# Top.net
KiCad netlist of a schematic drawn in Altium Designer
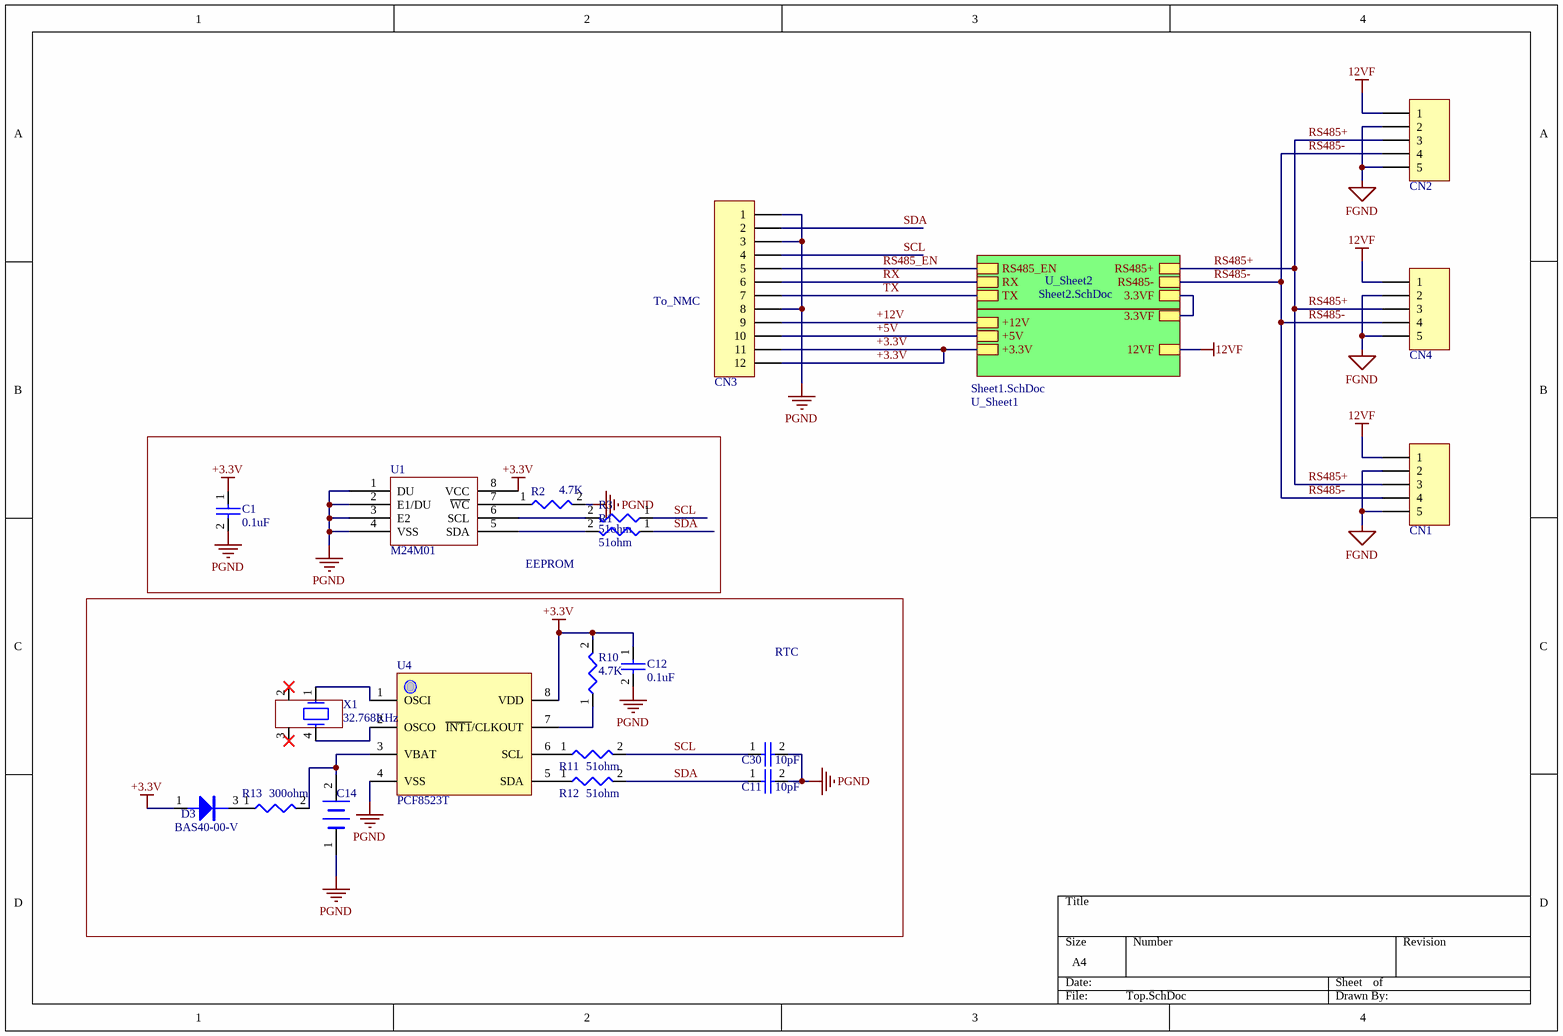
[diagram p0: Top.SchDoc]

(export (version "E")
  (design (tool "Eeschema 10.0.6"))
  (components
    (comp (ref "C1")
      (value "0.1uF")
      (footprint "C0805")
      (description "CAP SMD CR X7R 50V 10% 0.1uF 0805 ROHS")
      (fields (field (name "MANUFACTURER") "YAGEO") (field (name "Comment") "CAP"))
      (libsource (lib "enlogic") (part "CAP"))
    )
    (comp (ref "C11")
      (value "10pF")
      (footprint "C0805")
      (description "CAP SMD C0G 50V 10% 10pF 0805 ROHS")
      (fields (field (name "MANUFACTURER") "YAGEO") (field (name "Comment") "CAP"))
      (libsource (lib "enlogic") (part "CAP"))
    )
    (comp (ref "C12")
      (value "0.1uF")
      (footprint "C0805")
      (description "CAP SMD CR X7R 50V 10% 0.1uF 0805 ROHS")
      (fields (field (name "MANUFACTURER") "YAGEO") (field (name "Comment") "CAP"))
      (libsource (lib "enlogic") (part "CAP"))
    )
    (comp (ref "C14")
      (value "BATTERY")
      (footprint "DXJ_5R5H334U")
      (description "CAP Super Capacitor,5.5V 0.33F 11.5X5MM ROHS")
      (fields (field (name "MANUFACTURER") "ELNA"))
      (libsource (lib "enlogic") (part "BATTERY"))
    )
    (comp (ref "C30")
      (value "10pF")
      (footprint "C0805")
      (description "CAP SMD C0G 50V 10% 10pF 0805 ROHS")
      (fields (field (name "MANUFACTURER") "YAGEO") (field (name "Comment") "CAP"))
      (libsource (lib "enlogic") (part "CAP"))
    )
    (comp (ref "CN1")
      (value "Header 5")
      (footprint "70551-5P")
      (description "CONNECTOR 5PIN,2.54PITCH,90 Degrees,PTH")
      (fields (field (name "MANUFACTURER") "MOLEX"))
      (libsource (lib "enlogic") (part "Header 5"))
    )
    (comp (ref "CN2")
      (value "Header 5")
      (footprint "532590529")
      (description "CONNECTOR 5PIN,3.5PITCH,PTH,ROHS")
      (fields (field (name "MANUFACTURER") "MOLEX"))
      (libsource (lib "enlogic") (part "Header 5"))
    )
    (comp (ref "CN3")
      (value "Header 12")
      (footprint "353621276P2")
      (description "CONNECTOR 12PIN,2.00PITCH,PTH,2A,125V,ROHS,MATE_WITH:35507")
      (fields (field (name "MANUFACTURER") "MOLEX"))
      (libsource (lib "enlogic") (part "Header 12"))
    )
    (comp (ref "CN4")
      (value "Header 5")
      (footprint "70551-5P")
      (description "CONNECTOR 5PIN,2.54PITCH,90 Degrees,PTH")
      (fields (field (name "MANUFACTURER") "MOLEX"))
      (libsource (lib "enlogic") (part "Header 5"))
    )
    (comp (ref "D3")
      (value "BAS40-00-V")
      (footprint "SOT23-123")
      (description "DIODE Schottky Diode 40V 0.2A SOT-23 SMD ROHS")
      (fields (field (name "MANUFACTURER") "VISHAY"))
      (libsource (lib "enlogic") (part "BAS40-00-V"))
    )
    (comp (ref "R1")
      (value "51ohm")
      (footprint "R0805")
      (description "RES THICK_FILM SMD 51 OHM 5% 1/8W ROHS 0805")
      (fields (field (name "MANUFACTURER") "YAGEO") (field (name "Comment") "RES"))
      (libsource (lib "enlogic") (part "RES"))
    )
    (comp (ref "R2")
      (value "4.7K")
      (footprint "R0805")
      (description "RES THICK_FILM SMD 4.7K 5% 1/8W ROHS 0805")
      (fields (field (name "MANUFACTURER") "YAGEO") (field (name "Comment") "RES"))
      (libsource (lib "enlogic") (part "RES"))
    )
    (comp (ref "R3")
      (value "51ohm")
      (footprint "R0805")
      (description "RES THICK_FILM SMD 51 OHM 5% 1/8W ROHS 0805")
      (fields (field (name "MANUFACTURER") "YAGEO") (field (name "Comment") "RES"))
      (libsource (lib "enlogic") (part "RES"))
    )
    (comp (ref "R10")
      (value "4.7K")
      (footprint "R0805")
      (description "RES THICK_FILM SMD 4.7K 5% 1/8W ROHS 0805")
      (fields (field (name "MANUFACTURER") "YAGEO") (field (name "Comment") "RES"))
      (libsource (lib "enlogic") (part "RES"))
    )
    (comp (ref "R11")
      (value "51ohm")
      (footprint "R0805")
      (description "RES THICK_FILM SMD 51 OHM 5% 1/8W ROHS 0805")
      (fields (field (name "MANUFACTURER") "YAGEO") (field (name "Comment") "RES"))
      (libsource (lib "enlogic") (part "RES"))
    )
    (comp (ref "R12")
      (value "51ohm")
      (footprint "R0805")
      (description "RES THICK_FILM SMD 51 OHM 5% 1/8W ROHS 0805")
      (fields (field (name "MANUFACTURER") "YAGEO") (field (name "Comment") "RES"))
      (libsource (lib "enlogic") (part "RES"))
    )
    (comp (ref "R13")
      (value "300ohm")
      (footprint "R1206")
      (description "RES THICK_FILM SMD 300 OHM 1% 1/4W ROHS 1206")
      (fields (field (name "MANUFACTURER") "YAGEO") (field (name "Comment") "RES"))
      (libsource (lib "enlogic") (part "RES"))
    )
    (comp (ref "U1")
      (value "M24M01")
      (footprint "SOIC8")
      (description "IC 1-Mbit serial I2C bus EEPROM")
      (fields (field (name "MANUFACTURER") "ST"))
      (libsource (lib "enlogic") (part "M24M01"))
    )
    (comp (ref "U4")
      (value "PCF8523T")
      (footprint "SO-8")
      (description "IC Real-Time Clock (RTC) and calendar,SO8，ROHS")
      (fields (field (name "MANUFACTURER") "NXP"))
      (libsource (lib "enlogic") (part "PCF8523T"))
    )
    (comp (ref "X1")
      (value "32.768KHz")
      (footprint "MC306")
      (description "XTAL 8.0*3.8*2.5 32.768KHZ 6PF, +/-20PPM,SMD ROHS")
      (fields
        (field (name "MANUFACTURER") "Atop Electronic Technology Co.,Ltd.")
        (field (name "Comment") "MC306")
      )
      (libsource (lib "enlogic") (part "MC306"))
    )
  )
  (nets
    (net (code "1") (name "+3.3V") (class "Default")
      (node (ref "C1") (pin "1") (pinfunction "1_1") (pintype "passive"))
      (node (ref "C12") (pin "1") (pinfunction "1_1") (pintype "passive"))
      (node (ref "CN3") (pin "11") (pinfunction "11_11") (pintype "passive"))
      (node (ref "CN3") (pin "12") (pinfunction "12_12") (pintype "passive"))
      (node (ref "D3") (pin "1") (pinfunction "1_1") (pintype "passive"))
      (node (ref "R10") (pin "2") (pinfunction "2_2") (pintype "passive"))
      (node (ref "U1") (pin "8") (pinfunction "VCC_8") (pintype "passive"))
      (node (ref "U4") (pin "8") (pinfunction "VDD_8") (pintype "passive"))
    )
    (net (code "2") (name "/+5V") (class "Default")
      (node (ref "CN3") (pin "10") (pinfunction "10_10") (pintype "passive"))
    )
    (net (code "3") (name "/+12V") (class "Default")
      (node (ref "CN3") (pin "9") (pinfunction "9_9") (pintype "passive"))
    )
    (net (code "5") (name "/RS485+") (class "Default")
      (node (ref "CN1") (pin "3") (pinfunction "3_3") (pintype "passive"))
      (node (ref "CN2") (pin "3") (pinfunction "3_3") (pintype "passive"))
      (node (ref "CN4") (pin "3") (pinfunction "3_3") (pintype "passive"))
    )
    (net (code "6") (name "/RS485-") (class "Default")
      (node (ref "CN1") (pin "4") (pinfunction "4_4") (pintype "passive"))
      (node (ref "CN2") (pin "4") (pinfunction "4_4") (pintype "passive"))
      (node (ref "CN4") (pin "4") (pinfunction "4_4") (pintype "passive"))
    )
    (net (code "7") (name "/RS485_EN") (class "Default")
      (node (ref "CN3") (pin "5") (pinfunction "5_5") (pintype "passive"))
    )
    (net (code "8") (name "/RX") (class "Default")
      (node (ref "CN3") (pin "6") (pinfunction "6_6") (pintype "passive"))
    )
    (net (code "9") (name "/SCL") (class "Default")
      (node (ref "C30") (pin "1") (pinfunction "1_1") (pintype "passive"))
      (node (ref "CN3") (pin "4") (pinfunction "4_4") (pintype "passive"))
      (node (ref "R11") (pin "2") (pinfunction "2_2") (pintype "passive"))
      (node (ref "R3") (pin "1") (pinfunction "1_1") (pintype "passive"))
    )
    (net (code "10") (name "/SDA") (class "Default")
      (node (ref "C11") (pin "1") (pinfunction "1_1") (pintype "passive"))
      (node (ref "CN3") (pin "2") (pinfunction "2_2") (pintype "passive"))
      (node (ref "R1") (pin "1") (pinfunction "1_1") (pintype "passive"))
      (node (ref "R12") (pin "2") (pinfunction "2_2") (pintype "passive"))
    )
    (net (code "11") (name "/TX") (class "Default")
      (node (ref "CN3") (pin "7") (pinfunction "7_7") (pintype "passive"))
    )
    (net (code "12") (name "12VF") (class "Default")
      (node (ref "CN1") (pin "1") (pinfunction "1_1") (pintype "passive"))
      (node (ref "CN2") (pin "1") (pinfunction "1_1") (pintype "passive"))
      (node (ref "CN4") (pin "1") (pinfunction "1_1") (pintype "passive"))
    )
    (net (code "13") (name "FGND") (class "Default")
      (node (ref "CN1") (pin "2") (pinfunction "2_2") (pintype "passive"))
      (node (ref "CN1") (pin "5") (pinfunction "5_5") (pintype "passive"))
      (node (ref "CN2") (pin "2") (pinfunction "2_2") (pintype "passive"))
      (node (ref "CN2") (pin "5") (pinfunction "5_5") (pintype "passive"))
      (node (ref "CN4") (pin "2") (pinfunction "2_2") (pintype "passive"))
      (node (ref "CN4") (pin "5") (pinfunction "5_5") (pintype "passive"))
    )
    (net (code "14") (name "Net-(C14-+)") (class "Default")
      (node (ref "C14") (pin "2") (pinfunction "+_2") (pintype "passive"))
      (node (ref "R13") (pin "2") (pinfunction "2_2") (pintype "passive"))
      (node (ref "U4") (pin "3") (pinfunction "VBAT_3") (pintype "passive"))
    )
    (net (code "15") (name "Net-(D3-Pad3)") (class "Default")
      (node (ref "D3") (pin "3") (pinfunction "3_3") (pintype "passive"))
      (node (ref "R13") (pin "1") (pinfunction "1_1") (pintype "passive"))
    )
    (net (code "16") (name "Net-(U1-SCL)") (class "Default")
      (node (ref "R3") (pin "2") (pinfunction "2_2") (pintype "passive"))
      (node (ref "U1") (pin "6") (pinfunction "SCL_6") (pintype "passive"))
    )
    (net (code "17") (name "Net-(U1-SDA)") (class "Default")
      (node (ref "R1") (pin "2") (pinfunction "2_2") (pintype "passive"))
      (node (ref "U1") (pin "5") (pinfunction "SDA_5") (pintype "passive"))
    )
    (net (code "18") (name "Net-(U1-~{WC})") (class "Default")
      (node (ref "R2") (pin "1") (pinfunction "1_1") (pintype "passive"))
      (node (ref "U1") (pin "7") (pinfunction "~{WC}_7") (pintype "passive"))
    )
    (net (code "19") (name "Net-(U4-OSCI)") (class "Default")
      (node (ref "U4") (pin "1") (pinfunction "OSCI_1") (pintype "passive"))
      (node (ref "X1") (pin "1") (pinfunction "1_1") (pintype "passive"))
    )
    (net (code "20") (name "Net-(U4-OSCO)") (class "Default")
      (node (ref "U4") (pin "2") (pinfunction "OSCO_2") (pintype "passive"))
      (node (ref "X1") (pin "4") (pinfunction "4_4") (pintype "passive"))
    )
    (net (code "21") (name "Net-(U4-SCL)") (class "Default")
      (node (ref "R11") (pin "1") (pinfunction "1_1") (pintype "passive"))
      (node (ref "U4") (pin "6") (pinfunction "SCL_6") (pintype "passive"))
    )
    (net (code "22") (name "Net-(U4-SDA)") (class "Default")
      (node (ref "R12") (pin "1") (pinfunction "1_1") (pintype "passive"))
      (node (ref "U4") (pin "5") (pinfunction "SDA_5") (pintype "passive"))
    )
    (net (code "23") (name "Net-(U4-~{INT1}{slash}CLKOUT)") (class "Default")
      (node (ref "R10") (pin "1") (pinfunction "1_1") (pintype "passive"))
      (node (ref "U4") (pin "7") (pinfunction "~{INT1}/CLKOUT_7") (pintype "passive"))
    )
    (net (code "24") (name "PGND") (class "Default")
      (node (ref "C1") (pin "2") (pinfunction "2_2") (pintype "passive"))
      (node (ref "C11") (pin "2") (pinfunction "2_2") (pintype "passive"))
      (node (ref "C12") (pin "2") (pinfunction "2_2") (pintype "passive"))
      (node (ref "C14") (pin "1") (pinfunction "-_1") (pintype "passive"))
      (node (ref "C30") (pin "2") (pinfunction "2_2") (pintype "passive"))
      (node (ref "CN3") (pin "1") (pinfunction "1_1") (pintype "passive"))
      (node (ref "CN3") (pin "3") (pinfunction "3_3") (pintype "passive"))
      (node (ref "CN3") (pin "8") (pinfunction "8_8") (pintype "passive"))
      (node (ref "R2") (pin "2") (pinfunction "2_2") (pintype "passive"))
      (node (ref "U1") (pin "1") (pinfunction "DU_1") (pintype "passive"))
      (node (ref "U1") (pin "2") (pinfunction "E1/DU_2") (pintype "passive"))
      (node (ref "U1") (pin "3") (pinfunction "E2_3") (pintype "passive"))
      (node (ref "U1") (pin "4") (pinfunction "VSS_4") (pintype "passive"))
      (node (ref "U4") (pin "4") (pinfunction "VSS_4") (pintype "passive"))
    )
    (net (code "25") (name "unconnected-(X1-Pad2)") (class "Default")
      (node (ref "X1") (pin "2") (pinfunction "2_2") (pintype "passive+no_connect"))
    )
    (net (code "26") (name "unconnected-(X1-Pad3)") (class "Default")
      (node (ref "X1") (pin "3") (pinfunction "3_3") (pintype "passive+no_connect"))
    )
  )
)
